# -_-.net
KiCad netlist of a schematic drawn in Altium Designer
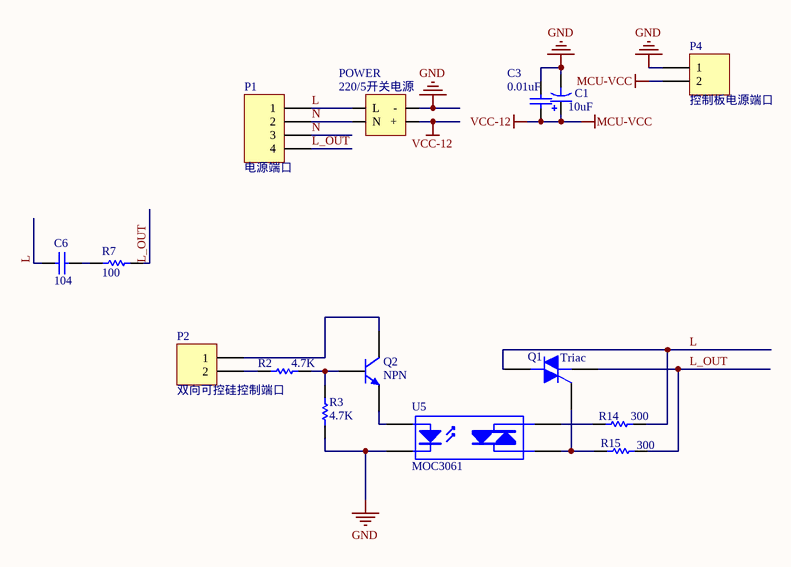
[diagram p0: 智能家居-电灯-电力板.SchDoc]

(export (version "E")
  (design (tool "Eeschema 10.0.6"))
  (components
    (comp (ref "C1")
      (value "10uF")
      (footprint "CD5")
      (description "Polarized Capacitor (Radial)")
      (fields (field (name "Comment") "Cap Pol1") (field (name "PUBLISHER") "Altium Limited"))
      (libsource (lib "Miscellaneous Devices") (part "Cap Pol1"))
    )
    (comp (ref "C3")
      (value "0.01uF")
      (footprint "0.1UF")
      (description "Capacitor")
      (fields (field (name "PUBLISHER") "Altium Limited"))
      (libsource (lib "Miscellaneous Devices") (part "Cap"))
    )
    (comp (ref "C6")
      (value "104")
      (footprint "0.1UF/275V")
      (description "Capacitor")
      (fields (field (name "Comment") "Cap") (field (name "PUBLISHER") "Altium Limited"))
      (libsource (lib "Miscellaneous Devices") (part "Cap"))
    )
    (comp (ref "P1")
      (value "电源端口")
      (footprint "JK128-500-4P")
      (description "Header, 4-Pin")
      (fields (field (name "PUBLISHER") "Altium Limited"))
      (libsource (lib "Miscellaneous Connectors") (part "Header 4"))
    )
    (comp (ref "P2")
      (value "双向可控硅控制端口")
      (footprint "TJC3-2A")
      (description "Header, 2-Pin")
      (fields (field (name "PUBLISHER") "Altium Limited"))
      (libsource (lib "") (part "Header 2_1"))
    )
    (comp (ref "P4")
      (value "控制板电源端口")
      (footprint "TJC3-2A")
      (description "Header, 2-Pin")
      (fields (field (name "PUBLISHER") "Altium Limited"))
      (libsource (lib "Miscellaneous Connectors") (part "Header 2"))
    )
    (comp (ref "POWER")
      (value "220/5开关电源")
      (footprint "220/5开关电源")
      (libsource (lib "杂元件库") (part "220/5开关电源"))
    )
    (comp (ref "Q1")
      (value "Triac")
      (footprint "TO-220(2)")
      (description "Silicon Bidirectional Triode Thyristor")
      (fields (field (name "PUBLISHER") "Altium Limited"))
      (libsource (lib "Miscellaneous Devices") (part "Triac"))
    )
    (comp (ref "Q2")
      (value "NPN")
      (footprint "TO-92D")
      (description "NPN Bipolar Transistor")
      (fields (field (name "PUBLISHER") "Altium Limited"))
      (libsource (lib "Miscellaneous Devices") (part "NPN"))
    )
    (comp (ref "R2")
      (value "4.7K")
      (description "Resistor")
      (fields (field (name "PUBLISHER") "Altium Limited"))
      (libsource (lib "Miscellaneous Devices") (part "Res1"))
    )
    (comp (ref "R3")
      (value "4.7K")
      (description "Resistor")
      (fields (field (name "PUBLISHER") "Altium Limited"))
      (libsource (lib "Miscellaneous Devices") (part "Res1"))
    )
    (comp (ref "R7")
      (value "100")
      (description "Resistor")
      (fields (field (name "PUBLISHER") "Altium Limited"))
      (libsource (lib "Miscellaneous Devices") (part "Res1"))
    )
    (comp (ref "R14")
      (value "300")
      (description "Resistor")
      (fields (field (name "PUBLISHER") "Altium Limited"))
      (libsource (lib "Miscellaneous Devices") (part "Res1"))
    )
    (comp (ref "R15")
      (value "300")
      (description "Resistor")
      (fields (field (name "PUBLISHER") "Altium Limited"))
      (libsource (lib "Miscellaneous Devices") (part "Res1"))
    )
    (comp (ref "U5") (value "MOC3061") (footprint "DIP-6N") (libsource (lib "杂元件库") (part "OPTOTRIAC")))
  )
  (nets
    (net (code "1") (name "/L") (class "Default")
      (node (ref "C6") (pin "2") (pinfunction "2_2") (pintype "passive"))
      (node (ref "P1") (pin "1") (pinfunction "1_1") (pintype "passive"))
      (node (ref "POWER") (pin "1") (pinfunction "L_1") (pintype "power_in"))
      (node (ref "Q1") (pin "2") (pinfunction "M2_2") (pintype "passive"))
      (node (ref "R14") (pin "1") (pinfunction "1_1") (pintype "passive"))
    )
    (net (code "2") (name "/L_OUT") (class "Default")
      (node (ref "P1") (pin "4") (pinfunction "4_4") (pintype "passive"))
      (node (ref "Q1") (pin "1") (pinfunction "M1_1") (pintype "passive"))
      (node (ref "R15") (pin "1") (pinfunction "1_1") (pintype "passive"))
      (node (ref "R7") (pin "1") (pinfunction "1_1") (pintype "passive"))
    )
    (net (code "3") (name "/N") (class "Default")
      (node (ref "P1") (pin "2") (pinfunction "2_2") (pintype "passive"))
      (node (ref "P1") (pin "3") (pinfunction "3_3") (pintype "passive"))
      (node (ref "POWER") (pin "2") (pinfunction "N_2") (pintype "passive"))
    )
    (net (code "4") (name "GND") (class "Default")
      (node (ref "C1") (pin "2") (pinfunction "2_2") (pintype "passive"))
      (node (ref "C3") (pin "2") (pinfunction "2_2") (pintype "passive"))
      (node (ref "P4") (pin "1") (pinfunction "1_1") (pintype "passive"))
      (node (ref "POWER") (pin "3") (pinfunction "-_3") (pintype "passive"))
      (node (ref "R3") (pin "2") (pinfunction "2_2") (pintype "passive"))
      (node (ref "U5") (pin "2") (pinfunction "2_2") (pintype "passive"))
    )
    (net (code "5") (name "MCU-VCC") (class "Default")
      (node (ref "C1") (pin "1") (pinfunction "1_1") (pintype "passive"))
      (node (ref "C3") (pin "1") (pinfunction "1_1") (pintype "passive"))
      (node (ref "P4") (pin "2") (pinfunction "2_2") (pintype "passive"))
      (node (ref "POWER") (pin "4") (pinfunction "+_4") (pintype "passive"))
    )
    (net (code "6") (name "Net-(C6-Pad1)") (class "Default")
      (node (ref "C6") (pin "1") (pinfunction "1_1") (pintype "passive"))
      (node (ref "R7") (pin "2") (pinfunction "2_2") (pintype "passive"))
    )
    (net (code "7") (name "Net-(P2-Pad2)") (class "Default")
      (node (ref "P2") (pin "2") (pinfunction "2_2") (pintype "passive"))
      (node (ref "R2") (pin "1") (pinfunction "1_1") (pintype "passive"))
    )
    (net (code "8") (name "Net-(Q1-G)") (class "Default")
      (node (ref "Q1") (pin "3") (pinfunction "G_3") (pintype "passive"))
      (node (ref "R15") (pin "2") (pinfunction "2_2") (pintype "passive"))
      (node (ref "U5") (pin "4") (pinfunction "A/K_4") (pintype "passive"))
    )
    (net (code "9") (name "Net-(Q2-B)") (class "Default")
      (node (ref "Q2") (pin "2") (pinfunction "B_2") (pintype "passive"))
      (node (ref "R2") (pin "2") (pinfunction "2_2") (pintype "passive"))
      (node (ref "R3") (pin "1") (pinfunction "1_1") (pintype "passive"))
    )
    (net (code "10") (name "Net-(Q2-C)") (class "Default")
      (node (ref "P2") (pin "1") (pinfunction "1_1") (pintype "passive"))
      (node (ref "Q2") (pin "3") (pinfunction "C_3") (pintype "passive"))
    )
    (net (code "11") (name "Net-(Q2-E)") (class "Default")
      (node (ref "Q2") (pin "1") (pinfunction "E_1") (pintype "passive"))
      (node (ref "U5") (pin "1") (pinfunction "1_1") (pintype "passive"))
    )
    (net (code "12") (name "Net-(R14-Pad2)") (class "Default")
      (node (ref "R14") (pin "2") (pinfunction "2_2") (pintype "passive"))
      (node (ref "U5") (pin "6") (pinfunction "6_6") (pintype "passive"))
    )
  )
)
